# BH66F5242-_Thermocouple.net
KiCad netlist of a schematic drawn in Altium Designer
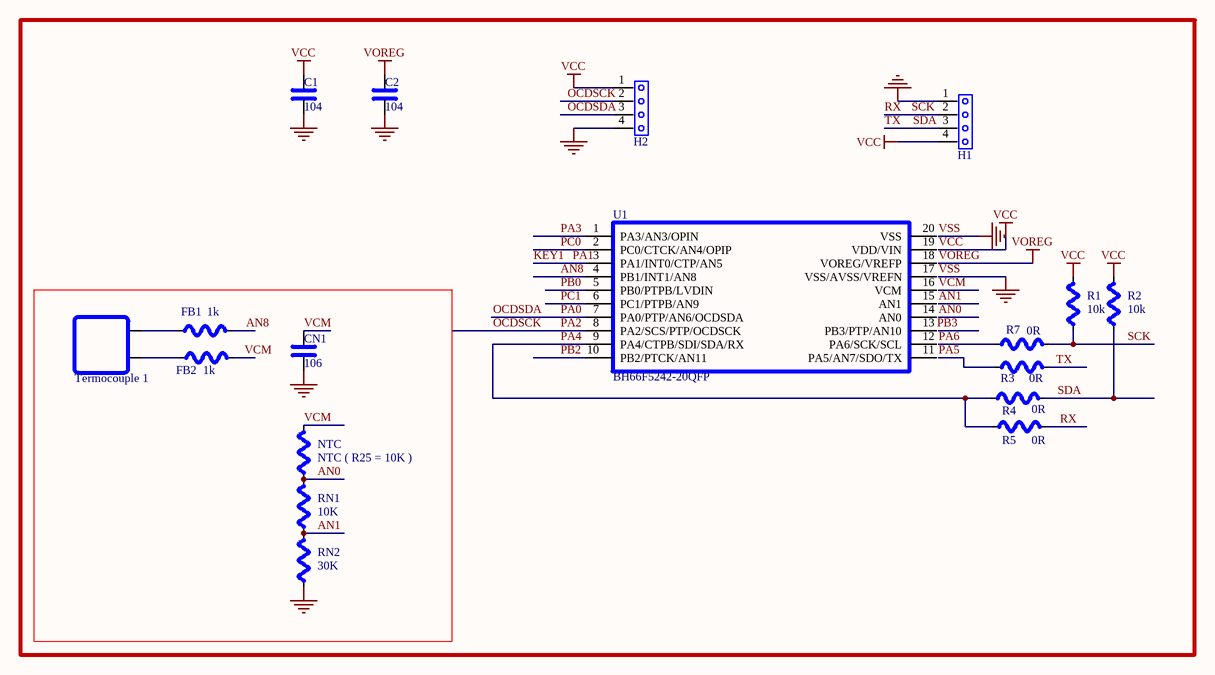
[diagram p0: BH66F5242- Thermocouple.SchDoc]

(export (version "E")
  (design (tool "Eeschema 10.0.6"))
  (components
    (comp (ref "C1")
      (value "104")
      (footprint "C0603")
      (description "0603 CAPACITOR")
      (fields (field (name "Comment") "CAP"))
      (libsource (lib "BH67F2470+BH66F2232") (part "C0603"))
    )
    (comp (ref "C2")
      (value "104")
      (footprint "C0603")
      (description "0603 CAPACITOR")
      (fields (field (name "Comment") "CAP"))
      (libsource (lib "BH67F2470+BH66F2232") (part "C0603"))
    )
    (comp (ref "CN1")
      (value "106")
      (footprint "C0603")
      (description "0603 CAPACITOR")
      (fields (field (name "Comment") "CAP"))
      (libsource (lib "BH67F2470+BH66F2232") (part "C0603"))
    )
    (comp (ref "FB1")
      (value "1k")
      (footprint "R0603")
      (description "RESISTOR")
      (libsource (lib "my_Y680_Component_Database(Miscellaneous)") (part "RESISTOR"))
    )
    (comp (ref "FB2")
      (value "1k")
      (footprint "R0603")
      (description "RESISTOR")
      (libsource (lib "my_Y680_Component_Database(Miscellaneous)") (part "RESISTOR"))
    )
    (comp (ref "H1")
      (value "HEADER4")
      (footprint "SIP4_2.0MM")
      (libsource (lib "my_Y680_Component_Database(Miscellaneous)") (part "HEADER4"))
    )
    (comp (ref "H2")
      (value "HEADER4")
      (footprint "HDR1X4")
      (libsource (lib "my_Y680_Component_Database(Miscellaneous)") (part "HEADER4"))
    )
    (comp (ref "NTC")
      (value "RES")
      (footprint "R0603")
      (description "0603 RESISTOR")
      (fields (field (name "VAULE") "NTC ( R25 = 10K )"))
      (libsource (lib "Y680_Component_Database") (part "R0603"))
    )
    (comp (ref "R1")
      (value "RES")
      (footprint "R0603")
      (description "0603 RESISTOR")
      (fields (field (name "VAULE") "10k"))
      (libsource (lib "Y680_Component_Database") (part "R0603"))
    )
    (comp (ref "R2")
      (value "RES")
      (footprint "R0603")
      (description "0603 RESISTOR")
      (fields (field (name "VAULE") "10k"))
      (libsource (lib "Y680_Component_Database") (part "R0603"))
    )
    (comp (ref "R3")
      (value "0R")
      (footprint "R0603")
      (description "RESISTOR")
      (libsource (lib "my_Y680_Component_Database(Miscellaneous)") (part "RESISTOR"))
    )
    (comp (ref "R4")
      (value "0R")
      (footprint "R0603")
      (description "RESISTOR")
      (libsource (lib "my_Y680_Component_Database(Miscellaneous)") (part "RESISTOR"))
    )
    (comp (ref "R5")
      (value "0R")
      (footprint "R0603")
      (description "RESISTOR")
      (libsource (lib "my_Y680_Component_Database(Miscellaneous)") (part "RESISTOR"))
    )
    (comp (ref "R7")
      (value "0R")
      (footprint "R0603")
      (description "RESISTOR")
      (libsource (lib "my_Y680_Component_Database(Miscellaneous)") (part "RESISTOR"))
    )
    (comp (ref "RN1")
      (value "RES")
      (footprint "R0603")
      (description "0603 RESISTOR")
      (fields (field (name "VAULE") "10K"))
      (libsource (lib "Y680_Component_Database") (part "R0603"))
    )
    (comp (ref "RN2")
      (value "RES")
      (footprint "R0603")
      (description "0603 RESISTOR")
      (fields (field (name "VAULE") "30K"))
      (libsource (lib "Y680_Component_Database") (part "R0603"))
    )
    (comp (ref "Termocouple 1")
      (value "CONNET*2")
      (footprint "KB396")
      (description "2CONNET*2.54")
      (libsource (lib "Y680_Component_Database(Miscellaneous)") (part "CONNET*2"))
    )
    (comp (ref "U1")
      (value "BH66F5242-20QFP")
      (footprint "QFN20(4*4)")
      (libsource (lib "PCB_Project4") (part "BH66F5242-20QFP"))
    )
  )
  (nets
    (net (code "1") (name "/AN0") (class "Default")
      (node (ref "NTC") (pin "1") (pinfunction "1_1") (pintype "passive"))
      (node (ref "RN1") (pin "2") (pinfunction "2_2") (pintype "passive"))
    )
    (net (code "2") (name "/AN1") (class "Default")
      (node (ref "RN1") (pin "1") (pinfunction "1_1") (pintype "passive"))
      (node (ref "RN2") (pin "2") (pinfunction "2_2") (pintype "passive"))
    )
    (net (code "3") (name "/AN8") (class "Default")
      (node (ref "FB1") (pin "2") (pinfunction "2_2") (pintype "passive"))
      (node (ref "U1") (pin "4") (pinfunction "PB1/INT1/AN8_4") (pintype "passive"))
    )
    (net (code "4") (name "/KEY1") (class "Default")
      (node (ref "U1") (pin "3") (pinfunction "PA1/INT0/CTP/AN5_3") (pintype "passive"))
    )
    (net (code "5") (name "/OCDSCK") (class "Default")
      (node (ref "H2") (pin "2") (pintype "passive"))
      (node (ref "U1") (pin "8") (pinfunction "PA2/SCS/PTP/OCDSCK_8") (pintype "passive"))
    )
    (net (code "6") (name "/OCDSDA") (class "Default")
      (node (ref "H2") (pin "3") (pintype "passive"))
      (node (ref "U1") (pin "7") (pinfunction "PA0/PTP/AN6/OCDSDA_7") (pintype "passive"))
    )
    (net (code "7") (name "/PA3") (class "Default")
      (node (ref "U1") (pin "1") (pinfunction "PA3/AN3/OPIN_1") (pintype "passive"))
    )
    (net (code "8") (name "/PA4") (class "Default")
      (node (ref "R4") (pin "1") (pinfunction "1_1") (pintype "passive"))
      (node (ref "R5") (pin "1") (pinfunction "1_1") (pintype "passive"))
      (node (ref "U1") (pin "9") (pinfunction "PA4/CTPB/SDI/SDA/RX_9") (pintype "passive"))
    )
    (net (code "9") (name "/PA5") (class "Default")
      (node (ref "R3") (pin "1") (pinfunction "1_1") (pintype "passive"))
    )
    (net (code "10") (name "/PA6") (class "Default")
      (node (ref "R7") (pin "1") (pinfunction "1_1") (pintype "passive"))
    )
    (net (code "11") (name "/PB0") (class "Default")
      (node (ref "U1") (pin "5") (pinfunction "PB0/PTPB/LVDIN_5") (pintype "passive"))
    )
    (net (code "12") (name "/PB2") (class "Default")
      (node (ref "U1") (pin "10") (pinfunction "PB2/PTCK/AN11_10") (pintype "passive"))
    )
    (net (code "13") (name "/PB3") (class "Default")
      (node (ref "U1") (pin "13") (pinfunction "PB3/PTP/AN10_13") (pintype "passive"))
    )
    (net (code "14") (name "/PC0") (class "Default")
      (node (ref "U1") (pin "2") (pinfunction "PC0/CTCK/AN4/OPIP_2") (pintype "passive"))
    )
    (net (code "15") (name "/PC1") (class "Default")
      (node (ref "U1") (pin "6") (pinfunction "PC1/PTPB/AN9_6") (pintype "passive"))
    )
    (net (code "16") (name "/RX") (class "Default")
      (node (ref "H1") (pin "2") (pintype "passive"))
      (node (ref "R1") (pin "1") (pinfunction "1_1") (pintype "passive"))
      (node (ref "R5") (pin "2") (pinfunction "2_2") (pintype "passive"))
      (node (ref "R7") (pin "2") (pinfunction "2_2") (pintype "passive"))
    )
    (net (code "17") (name "/SDA") (class "Default")
      (node (ref "H1") (pin "3") (pintype "passive"))
      (node (ref "R2") (pin "1") (pinfunction "1_1") (pintype "passive"))
      (node (ref "R3") (pin "2") (pinfunction "2_2") (pintype "passive"))
      (node (ref "R4") (pin "2") (pinfunction "2_2") (pintype "passive"))
    )
    (net (code "18") (name "/VCM") (class "Default")
      (node (ref "CN1") (pin "2") (pinfunction "2_2") (pintype "passive"))
      (node (ref "FB2") (pin "2") (pinfunction "2_2") (pintype "passive"))
      (node (ref "NTC") (pin "2") (pinfunction "2_2") (pintype "passive"))
    )
    (net (code "19") (name "GND") (class "Default")
      (node (ref "C1") (pin "1") (pinfunction "1_1") (pintype "passive"))
      (node (ref "C2") (pin "1") (pinfunction "1_1") (pintype "passive"))
      (node (ref "CN1") (pin "1") (pinfunction "1_1") (pintype "passive"))
      (node (ref "H1") (pin "1") (pintype "passive"))
      (node (ref "H2") (pin "4") (pintype "passive"))
      (node (ref "RN2") (pin "1") (pinfunction "1_1") (pintype "passive"))
    )
    (net (code "20") (name "Net-(FB1-Pad1)") (class "Default")
      (node (ref "FB1") (pin "1") (pinfunction "1_1") (pintype "passive"))
      (node (ref "Termocouple 1") (pin "2") (pinfunction "2_2") (pintype "passive"))
    )
    (net (code "21") (name "Net-(FB2-Pad1)") (class "Default")
      (node (ref "FB2") (pin "1") (pinfunction "1_1") (pintype "passive"))
      (node (ref "Termocouple 1") (pin "1") (pinfunction "1_1") (pintype "passive"))
    )
    (net (code "22") (name "VCC") (class "Default")
      (node (ref "C1") (pin "2") (pinfunction "2_2") (pintype "passive"))
      (node (ref "H1") (pin "4") (pintype "passive"))
      (node (ref "H2") (pin "1") (pintype "passive"))
      (node (ref "R1") (pin "2") (pinfunction "2_2") (pintype "passive"))
      (node (ref "R2") (pin "2") (pinfunction "2_2") (pintype "passive"))
    )
    (net (code "23") (name "VOREG") (class "Default")
      (node (ref "C2") (pin "2") (pinfunction "2_2") (pintype "passive"))
    )
    (net (code "24") (name "unconnected-(U1-AN0-Pad14)") (class "Default")
      (node (ref "U1") (pin "14") (pinfunction "AN0_14") (pintype "passive"))
    )
    (net (code "25") (name "unconnected-(U1-AN1-Pad15)") (class "Default")
      (node (ref "U1") (pin "15") (pinfunction "AN1_15") (pintype "passive"))
    )
    (net (code "26") (name "unconnected-(U1-PA5{slash}AN7{slash}SDO{slash}TX-Pad11)") (class "Default")
      (node (ref "U1") (pin "11") (pinfunction "PA5/AN7/SDO/TX_11") (pintype "passive"))
    )
    (net (code "27") (name "unconnected-(U1-PA6{slash}SCK{slash}SCL-Pad12)") (class "Default")
      (node (ref "U1") (pin "12") (pinfunction "PA6/SCK/SCL_12") (pintype "passive"))
    )
    (net (code "28") (name "unconnected-(U1-VCM-Pad16)") (class "Default")
      (node (ref "U1") (pin "16") (pinfunction "VCM_16") (pintype "passive"))
    )
    (net (code "29") (name "unconnected-(U1-VDD{slash}VIN-Pad19)") (class "Default")
      (node (ref "U1") (pin "19") (pinfunction "VDD/VIN_19") (pintype "passive"))
    )
    (net (code "30") (name "unconnected-(U1-VOREG{slash}VREFP-Pad18)") (class "Default")
      (node (ref "U1") (pin "18") (pinfunction "VOREG/VREFP_18") (pintype "passive"))
    )
    (net (code "31") (name "unconnected-(U1-VSS-Pad20)") (class "Default")
      (node (ref "U1") (pin "20") (pinfunction "VSS_20") (pintype "passive"))
    )
    (net (code "32") (name "unconnected-(U1-VSS{slash}AVSS{slash}VREFN-Pad17)") (class "Default")
      (node (ref "U1") (pin "17") (pinfunction "VSS/AVSS/VREFN_17") (pintype "passive"))
    )
  )
)
